# waterLevelDisplay.net
KiCad netlist of a schematic drawn in EAGLE
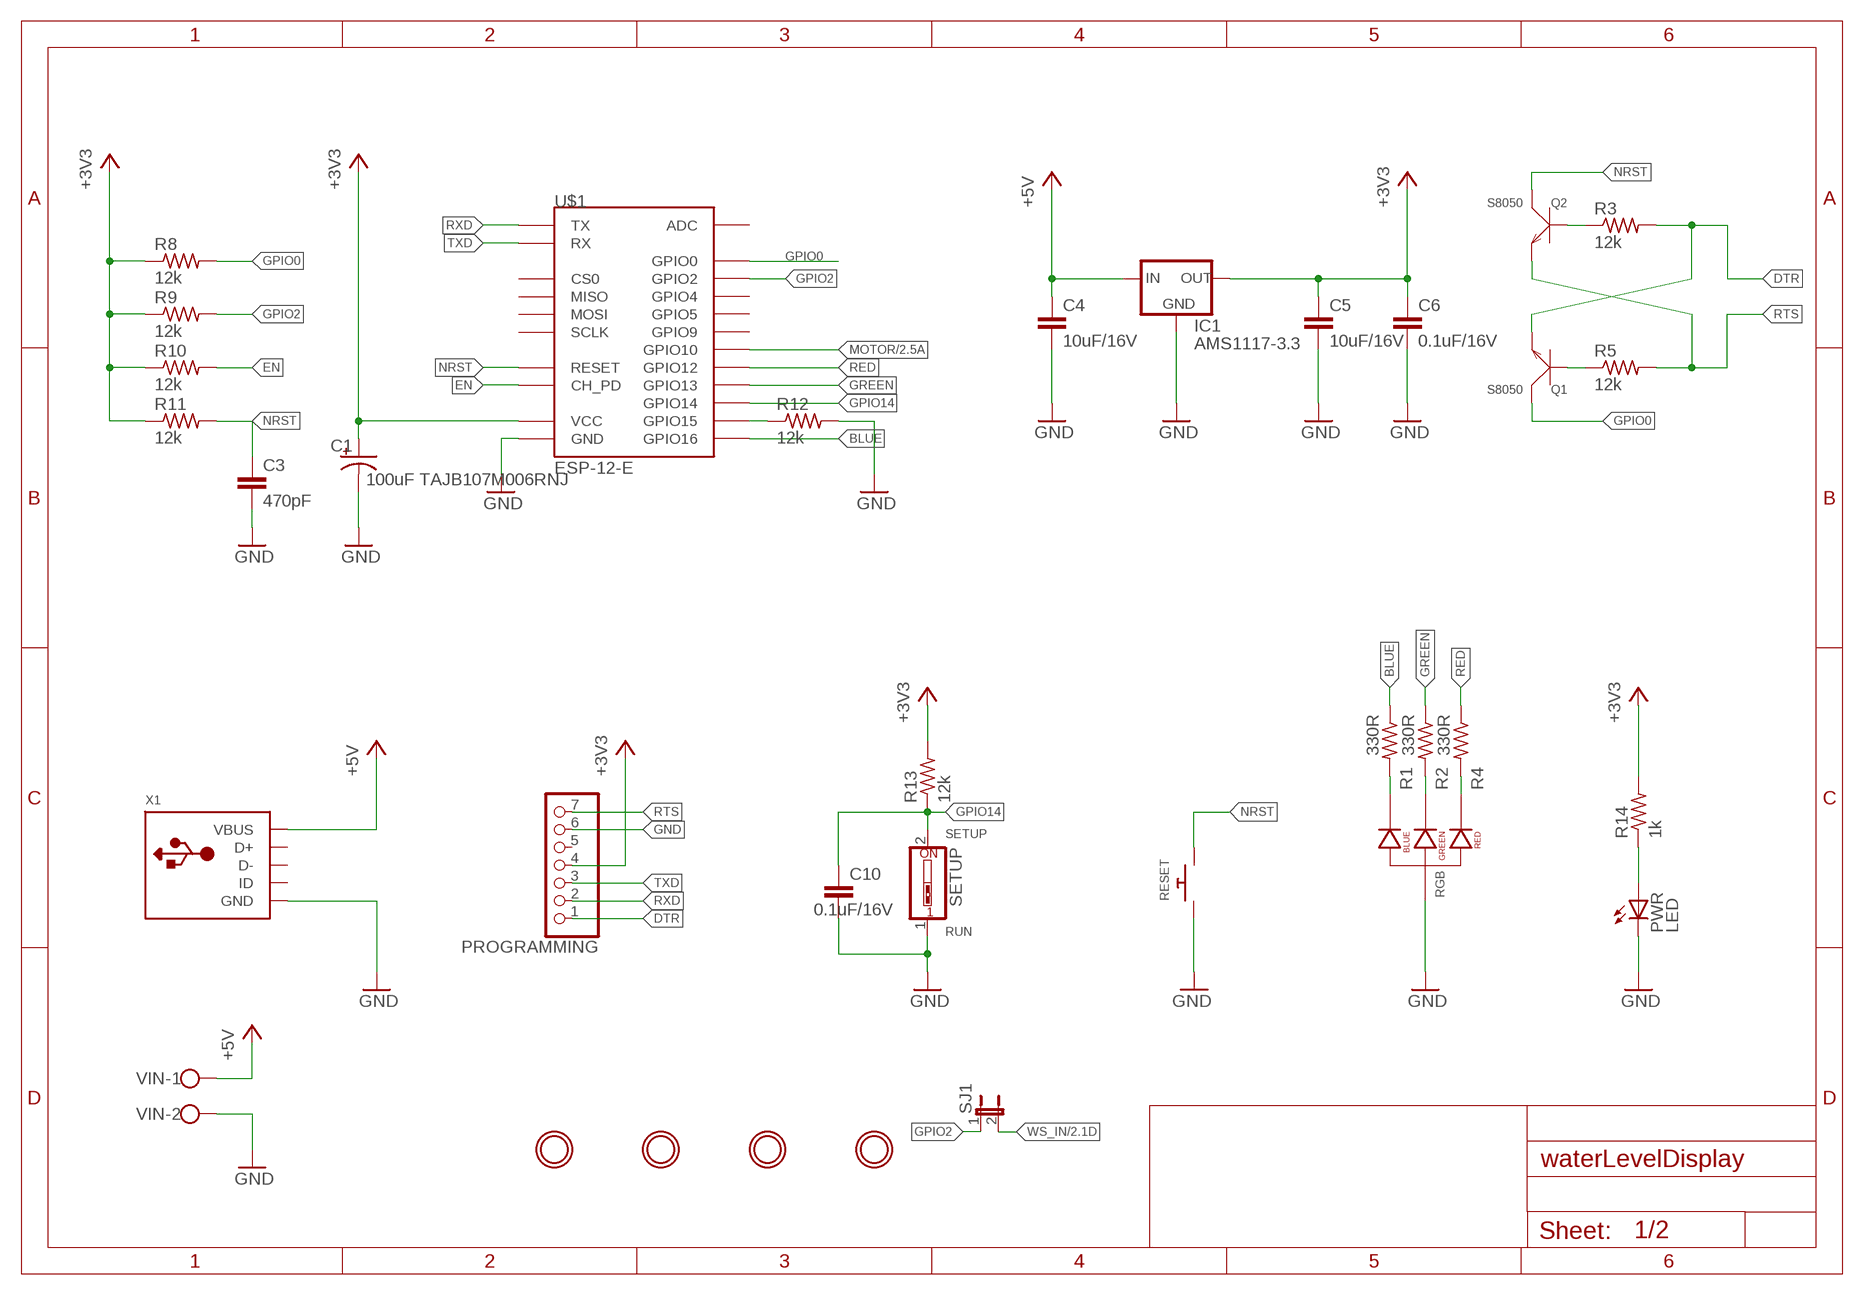
[diagram p0: schematic, sheet 1]
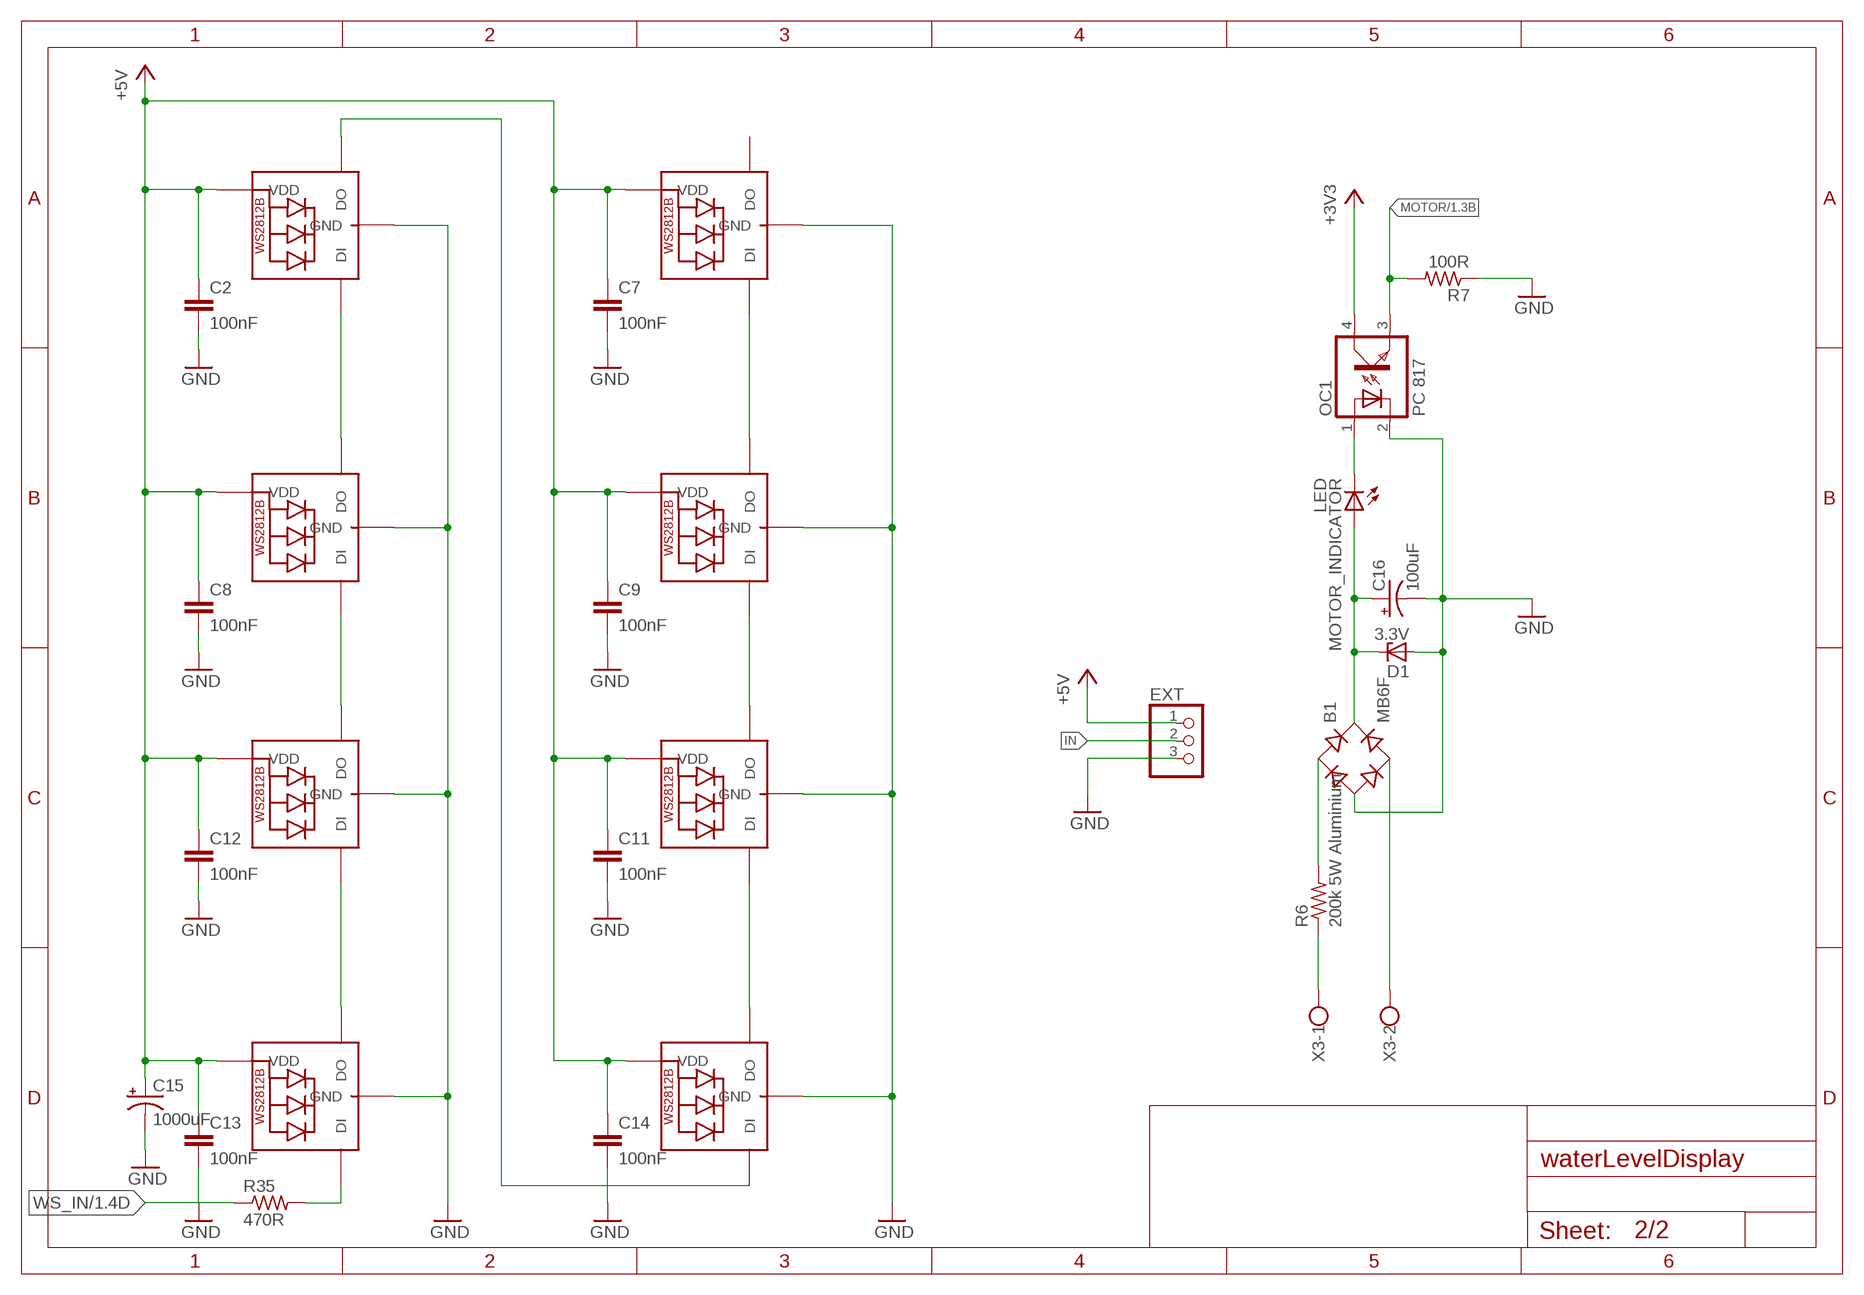
[diagram p1: schematic, sheet 2]

(export (version "E")
  (design (tool "Eeschema 10.0.6"))
  (components
    (comp (ref "B1")
      (value "MB6F")
      (footprint "eagle-import:SOIC-4")
      (libsource (lib "eagle-import") (part "MBS6"))
    )
    (comp (ref "C2")
      (value "100nF")
      (footprint "eagle-import:C0805K")
      (libsource (lib "eagle-import") (part "C-EUC0805K"))
    )
    (comp (ref "C7")
      (value "100nF")
      (footprint "eagle-import:C0805K")
      (libsource (lib "eagle-import") (part "C-EUC0805K"))
    )
    (comp (ref "C8")
      (value "100nF")
      (footprint "eagle-import:C0805K")
      (libsource (lib "eagle-import") (part "C-EUC0805K"))
    )
    (comp (ref "C9")
      (value "100nF")
      (footprint "eagle-import:C0805K")
      (libsource (lib "eagle-import") (part "C-EUC0805K"))
    )
    (comp (ref "C11")
      (value "100nF")
      (footprint "eagle-import:C0805K")
      (libsource (lib "eagle-import") (part "C-EUC0805K"))
    )
    (comp (ref "C12")
      (value "100nF")
      (footprint "eagle-import:C0805K")
      (libsource (lib "eagle-import") (part "C-EUC0805K"))
    )
    (comp (ref "C13")
      (value "100nF")
      (footprint "eagle-import:C0805K")
      (libsource (lib "eagle-import") (part "C-EUC0805K"))
    )
    (comp (ref "C14")
      (value "100nF")
      (footprint "eagle-import:C0805K")
      (libsource (lib "eagle-import") (part "C-EUC0805K"))
    )
    (comp (ref "C15")
      (value "1000uF")
      (footprint "eagle-import:E5-10,5")
      (libsource (lib "eagle-import") (part "CPOL-USE5-10.5"))
    )
    (comp (ref "C16")
      (value "100uF")
      (footprint "eagle-import:E2,5-7")
      (libsource (lib "eagle-import") (part "CPOL-USE2.5-7"))
    )
    (comp (ref "D1")
      (value "3.3V")
      (footprint "eagle-import:ZDIO-7.5")
      (libsource (lib "eagle-import") (part "ZENER-DIODEZD-7.5"))
    )
    (comp (ref "EXT")
      (value "PINHD-1X3")
      (footprint "eagle-import:1X03")
      (libsource (lib "eagle-import") (part "PINHD-1X3"))
    )
    (comp (ref "LED1")
      (value "WS2812B5050")
      (footprint "eagle-import:WS2812B")
      (libsource (lib "eagle-import") (part "WS2812B5050"))
    )
    (comp (ref "LED2")
      (value "WS2812B5050")
      (footprint "eagle-import:WS2812B")
      (libsource (lib "eagle-import") (part "WS2812B5050"))
    )
    (comp (ref "LED3")
      (value "WS2812B5050")
      (footprint "eagle-import:WS2812B")
      (libsource (lib "eagle-import") (part "WS2812B5050"))
    )
    (comp (ref "LED4")
      (value "WS2812B5050")
      (footprint "eagle-import:WS2812B")
      (libsource (lib "eagle-import") (part "WS2812B5050"))
    )
    (comp (ref "LED5")
      (value "WS2812B5050")
      (footprint "eagle-import:WS2812B")
      (libsource (lib "eagle-import") (part "WS2812B5050"))
    )
    (comp (ref "LED6")
      (value "WS2812B5050")
      (footprint "eagle-import:WS2812B")
      (libsource (lib "eagle-import") (part "WS2812B5050"))
    )
    (comp (ref "LED7")
      (value "WS2812B5050")
      (footprint "eagle-import:WS2812B")
      (libsource (lib "eagle-import") (part "WS2812B5050"))
    )
    (comp (ref "LED8")
      (value "WS2812B5050")
      (footprint "eagle-import:WS2812B")
      (libsource (lib "eagle-import") (part "WS2812B5050"))
    )
    (comp (ref "MOTOR_INDICATOR")
      (value "LED")
      (footprint "eagle-import:CHIP-LED0805")
      (libsource (lib "eagle-import") (part "LEDCHIP-LED0805"))
    )
    (comp (ref "OC1")
      (value "PC 817")
      (footprint "eagle-import:DIP4")
      (fields (field (name "MF") "VISHAY/TELEFUNKEN") (field (name "MPN") "SFH618A-3"))
      (libsource (lib "eagle-import") (part "SFH618?A-3"))
    )
    (comp (ref "R6")
      (value "200k 5W Aluminium")
      (footprint "eagle-import:0617_22")
      (libsource (lib "eagle-import") (part "R-US_0617/22"))
    )
    (comp (ref "R7")
      (value "100R")
      (footprint "eagle-import:M0805")
      (libsource (lib "eagle-import") (part "R-US_M0805"))
    )
    (comp (ref "R35")
      (value "470R")
      (footprint "eagle-import:M0805")
      (libsource (lib "eagle-import") (part "R-US_M0805"))
    )
    (comp (ref "X3")
      (value "W237-102")
      (footprint "eagle-import:W237-102")
      (fields (field (name "MPN") "237-102"))
      (libsource (lib "eagle-import") (part "W237-102"))
    )
    (comp (ref "C1")
      (value "100uF TAJB107M006RNJ")
      (footprint "eagle-import:A_3216-18R")
      (libsource (lib "eagle-import") (part "CPOL-USA/3216-18R"))
    )
    (comp (ref "C3")
      (value "470pF")
      (footprint "eagle-import:C0805K")
      (libsource (lib "eagle-import") (part "C-EUC0805K"))
    )
    (comp (ref "C4")
      (value "10uF/16V")
      (footprint "eagle-import:C0805K")
      (libsource (lib "eagle-import") (part "C-EUC0805K"))
    )
    (comp (ref "C5")
      (value "10uF/16V")
      (footprint "eagle-import:C0805K")
      (libsource (lib "eagle-import") (part "C-EUC0805K"))
    )
    (comp (ref "C6")
      (value "0.1uF/16V")
      (footprint "eagle-import:C0805K")
      (libsource (lib "eagle-import") (part "C-EUC0805K"))
    )
    (comp (ref "C10")
      (value "0.1uF/16V")
      (footprint "eagle-import:C0805K")
      (libsource (lib "eagle-import") (part "C-EUC0805K"))
    )
    (comp (ref "IC1")
      (value "AMS1117-3.3")
      (footprint "eagle-import:SOT223")
      (libsource (lib "eagle-import") (part "LM1117"))
    )
    (comp (ref "PROGRAMMING")
      (value "PINHD-1X7")
      (footprint "eagle-import:1X07")
      (libsource (lib "eagle-import") (part "PINHD-1X7"))
    )
    (comp (ref "PWR")
      (value "LED")
      (footprint "eagle-import:CHIP-LED0805")
      (libsource (lib "eagle-import") (part "LEDCHIP-LED0805"))
    )
    (comp (ref "Q1")
      (value "S8050")
      (footprint "eagle-import:SOT-23")
      (fields (field (name "MF") "JCET"))
      (libsource (lib "eagle-import") (part "SMD-TRANSISTORS-NPN-25V-500MW(SOT-23)"))
    )
    (comp (ref "Q2")
      (value "S8050")
      (footprint "eagle-import:SOT-23")
      (fields (field (name "MF") "JCET"))
      (libsource (lib "eagle-import") (part "SMD-TRANSISTORS-NPN-25V-500MW(SOT-23)"))
    )
    (comp (ref "R1")
      (value "330R")
      (footprint "eagle-import:M0805")
      (libsource (lib "eagle-import") (part "R-US_M0805"))
    )
    (comp (ref "R2")
      (value "330R")
      (footprint "eagle-import:M0805")
      (libsource (lib "eagle-import") (part "R-US_M0805"))
    )
    (comp (ref "R3")
      (value "12k")
      (footprint "eagle-import:M0805")
      (libsource (lib "eagle-import") (part "R-US_M0805"))
    )
    (comp (ref "R4")
      (value "330R")
      (footprint "eagle-import:M0805")
      (libsource (lib "eagle-import") (part "R-US_M0805"))
    )
    (comp (ref "R5")
      (value "12k")
      (footprint "eagle-import:M0805")
      (libsource (lib "eagle-import") (part "R-US_M0805"))
    )
    (comp (ref "R8")
      (value "12k")
      (footprint "eagle-import:M0805")
      (libsource (lib "eagle-import") (part "R-US_M0805"))
    )
    (comp (ref "R9")
      (value "12k")
      (footprint "eagle-import:M0805")
      (libsource (lib "eagle-import") (part "R-US_M0805"))
    )
    (comp (ref "R10")
      (value "12k")
      (footprint "eagle-import:M0805")
      (libsource (lib "eagle-import") (part "R-US_M0805"))
    )
    (comp (ref "R11")
      (value "12k")
      (footprint "eagle-import:M0805")
      (libsource (lib "eagle-import") (part "R-US_M0805"))
    )
    (comp (ref "R12")
      (value "12k")
      (footprint "eagle-import:M0805")
      (libsource (lib "eagle-import") (part "R-US_M0805"))
    )
    (comp (ref "R13")
      (value "12k")
      (footprint "eagle-import:M0805")
      (libsource (lib "eagle-import") (part "R-US_M0805"))
    )
    (comp (ref "R14")
      (value "1k")
      (footprint "eagle-import:M0805")
      (libsource (lib "eagle-import") (part "R-US_M0805"))
    )
    (comp (ref "RESET")
      (value "SWITCH_PUSHBUTTONEVQ-PE")
      (footprint "eagle-import:TACT_PANA-EVQ")
      (libsource (lib "eagle-import") (part "SWITCH_PUSHBUTTONEVQ-PE"))
    )
    (comp (ref "RGB")
      (value "LED-RGB-CA-THRUCLEAR")
      (footprint "eagle-import:LED-RGB-THRU")
      (libsource (lib "eagle-import") (part "LED-RGB-CA-THRUCLEAR"))
    )
    (comp (ref "SETUP")
      (value "SW_DIP-1")
      (footprint "eagle-import:EDG-01")
      (libsource (lib "eagle-import") (part "SW_DIP-1"))
    )
    (comp (ref "SJ1")
      (value "SPARKFUN-PASSIVES_JUMPER-PTH-2-NC")
      (footprint "eagle-import:SPARKFUN-PASSIVES_PTH-JUMPER-NC_BOTTOM_NO_SILK")
      (libsource (lib "eagle-import") (part "SPARKFUN-PASSIVES_JUMPER-PTH-2-NC"))
    )
    (comp (ref "U$1")
      (value "ESP-12-E")
      (footprint "eagle-import:ESP-12-E")
      (libsource (lib "eagle-import") (part "ESP-12-E"))
    )
    (comp (ref "U$3")
      (value "MOUNTINGHOLE2.5")
      (footprint "eagle-import:MOUNTINGHOLE_2.5_PLATED")
      (libsource (lib "eagle-import") (part "MOUNTINGHOLE2.5"))
    )
    (comp (ref "U$4")
      (value "MOUNTINGHOLE2.5")
      (footprint "eagle-import:MOUNTINGHOLE_2.5_PLATED")
      (libsource (lib "eagle-import") (part "MOUNTINGHOLE2.5"))
    )
    (comp (ref "U$5")
      (value "MOUNTINGHOLE2.5")
      (footprint "eagle-import:MOUNTINGHOLE_2.5_PLATED")
      (libsource (lib "eagle-import") (part "MOUNTINGHOLE2.5"))
    )
    (comp (ref "U$6")
      (value "MOUNTINGHOLE2.5")
      (footprint "eagle-import:MOUNTINGHOLE_2.5_PLATED")
      (libsource (lib "eagle-import") (part "MOUNTINGHOLE2.5"))
    )
    (comp (ref "VIN")
      (value "W237-102")
      (footprint "eagle-import:W237-102")
      (fields (field (name "MPN") "237-102"))
      (libsource (lib "eagle-import") (part "W237-102"))
    )
    (comp (ref "X1")
      (value "USB_MICRO_20329_V2")
      (footprint "eagle-import:4UCONN_20329_V2")
      (libsource (lib "eagle-import") (part "USB_MICRO_20329_V2"))
    )
  )
  (nets
    (net (code "1") (name "+3V3") (class "Default")
      (node (ref "C1") (pin "+") (pinfunction "+_+") (pintype "passive"))
      (node (ref "C5") (pin "1") (pinfunction "1_1") (pintype "passive"))
      (node (ref "C6") (pin "1") (pinfunction "1_1") (pintype "passive"))
      (node (ref "IC1") (pin "2") (pinfunction "OUT_2") (pintype "passive"))
      (node (ref "OC1") (pin "4") (pinfunction "COL_4") (pintype "passive"))
      (node (ref "PROGRAMMING") (pin "4") (pinfunction "4_4") (pintype "passive"))
      (node (ref "R10") (pin "1") (pinfunction "1_1") (pintype "passive"))
      (node (ref "R11") (pin "1") (pinfunction "1_1") (pintype "passive"))
      (node (ref "R13") (pin "2") (pinfunction "2_2") (pintype "passive"))
      (node (ref "R14") (pin "2") (pinfunction "2_2") (pintype "passive"))
      (node (ref "R8") (pin "1") (pinfunction "1_1") (pintype "passive"))
      (node (ref "R9") (pin "1") (pinfunction "1_1") (pintype "passive"))
      (node (ref "U$1") (pin "VCC") (pinfunction "VCC_VCC") (pintype "bidirectional"))
    )
    (net (code "2") (name "+5V") (class "Default")
      (node (ref "C11") (pin "1") (pinfunction "1_1") (pintype "passive"))
      (node (ref "C12") (pin "1") (pinfunction "1_1") (pintype "passive"))
      (node (ref "C13") (pin "1") (pinfunction "1_1") (pintype "passive"))
      (node (ref "C14") (pin "1") (pinfunction "1_1") (pintype "passive"))
      (node (ref "C15") (pin "+") (pinfunction "+_+") (pintype "passive"))
      (node (ref "C2") (pin "1") (pinfunction "1_1") (pintype "passive"))
      (node (ref "C4") (pin "1") (pinfunction "1_1") (pintype "passive"))
      (node (ref "C7") (pin "1") (pinfunction "1_1") (pintype "passive"))
      (node (ref "C8") (pin "1") (pinfunction "1_1") (pintype "passive"))
      (node (ref "C9") (pin "1") (pinfunction "1_1") (pintype "passive"))
      (node (ref "EXT") (pin "1") (pinfunction "1_1") (pintype "passive"))
      (node (ref "IC1") (pin "3") (pinfunction "IN_3") (pintype "input"))
      (node (ref "LED1") (pin "1-VDD") (pinfunction "VDD_1-VDD") (pintype "power_in"))
      (node (ref "LED2") (pin "1-VDD") (pinfunction "VDD_1-VDD") (pintype "power_in"))
      (node (ref "LED3") (pin "1-VDD") (pinfunction "VDD_1-VDD") (pintype "power_in"))
      (node (ref "LED4") (pin "1-VDD") (pinfunction "VDD_1-VDD") (pintype "power_in"))
      (node (ref "LED5") (pin "1-VDD") (pinfunction "VDD_1-VDD") (pintype "power_in"))
      (node (ref "LED6") (pin "1-VDD") (pinfunction "VDD_1-VDD") (pintype "power_in"))
      (node (ref "LED7") (pin "1-VDD") (pinfunction "VDD_1-VDD") (pintype "power_in"))
      (node (ref "LED8") (pin "1-VDD") (pinfunction "VDD_1-VDD") (pintype "power_in"))
      (node (ref "VIN") (pin "1") (pinfunction "KL_1") (pintype "passive"))
      (node (ref "X1") (pin "VBUS") (pinfunction "VBUS_VBUS") (pintype "power_in"))
    )
    (net (code "3") (name "BLUE") (class "Default")
      (node (ref "R1") (pin "1") (pinfunction "1_1") (pintype "passive"))
      (node (ref "U$1") (pin "GPIO16") (pinfunction "GPIO16_GPIO16") (pintype "bidirectional"))
    )
    (net (code "4") (name "DTR") (class "Default")
      (node (ref "PROGRAMMING") (pin "1") (pinfunction "1_1") (pintype "passive"))
      (node (ref "Q1") (pin "2") (pinfunction "E_2") (pintype "passive"))
      (node (ref "R3") (pin "2") (pinfunction "2_2") (pintype "passive"))
    )
    (net (code "5") (name "EN") (class "Default")
      (node (ref "R10") (pin "2") (pinfunction "2_2") (pintype "passive"))
      (node (ref "U$1") (pin "CH_PD") (pinfunction "CH_PD_CH_PD") (pintype "bidirectional"))
    )
    (net (code "6") (name "GND") (class "Default")
      (node (ref "B1") (pin "-") (pinfunction "-_-") (pintype "passive"))
      (node (ref "C1") (pin "-") (pinfunction "-_-") (pintype "passive"))
      (node (ref "C10") (pin "2") (pinfunction "2_2") (pintype "passive"))
      (node (ref "C11") (pin "2") (pinfunction "2_2") (pintype "passive"))
      (node (ref "C12") (pin "2") (pinfunction "2_2") (pintype "passive"))
      (node (ref "C13") (pin "2") (pinfunction "2_2") (pintype "passive"))
      (node (ref "C14") (pin "2") (pinfunction "2_2") (pintype "passive"))
      (node (ref "C15") (pin "-") (pinfunction "-_-") (pintype "passive"))
      (node (ref "C16") (pin "-") (pinfunction "-_-") (pintype "passive"))
      (node (ref "C2") (pin "2") (pinfunction "2_2") (pintype "passive"))
      (node (ref "C3") (pin "2") (pinfunction "2_2") (pintype "passive"))
      (node (ref "C4") (pin "2") (pinfunction "2_2") (pintype "passive"))
      (node (ref "C5") (pin "2") (pinfunction "2_2") (pintype "passive"))
      (node (ref "C6") (pin "2") (pinfunction "2_2") (pintype "passive"))
      (node (ref "C7") (pin "2") (pinfunction "2_2") (pintype "passive"))
      (node (ref "C8") (pin "2") (pinfunction "2_2") (pintype "passive"))
      (node (ref "C9") (pin "2") (pinfunction "2_2") (pintype "passive"))
      (node (ref "D1") (pin "A") (pinfunction "A_A") (pintype "passive"))
      (node (ref "EXT") (pin "3") (pinfunction "3_3") (pintype "passive"))
      (node (ref "IC1") (pin "1") (pinfunction "GND_1") (pintype "input"))
      (node (ref "LED1") (pin "3-GND") (pinfunction "GND_3-GND") (pintype "power_in"))
      (node (ref "LED2") (pin "3-GND") (pinfunction "GND_3-GND") (pintype "power_in"))
      (node (ref "LED3") (pin "3-GND") (pinfunction "GND_3-GND") (pintype "power_in"))
      (node (ref "LED4") (pin "3-GND") (pinfunction "GND_3-GND") (pintype "power_in"))
      (node (ref "LED5") (pin "3-GND") (pinfunction "GND_3-GND") (pintype "power_in"))
      (node (ref "LED6") (pin "3-GND") (pinfunction "GND_3-GND") (pintype "power_in"))
      (node (ref "LED7") (pin "3-GND") (pinfunction "GND_3-GND") (pintype "power_in"))
      (node (ref "LED8") (pin "3-GND") (pinfunction "GND_3-GND") (pintype "power_in"))
      (node (ref "OC1") (pin "2") (pinfunction "C_2") (pintype "passive"))
      (node (ref "PROGRAMMING") (pin "6") (pinfunction "6_6") (pintype "passive"))
      (node (ref "PWR") (pin "C") (pinfunction "C_C") (pintype "passive"))
      (node (ref "R12") (pin "2") (pinfunction "2_2") (pintype "passive"))
      (node (ref "R7") (pin "1") (pinfunction "1_1") (pintype "passive"))
      (node (ref "RESET") (pin "P$1") (pinfunction "P$1_P$1") (pintype "passive"))
      (node (ref "RGB") (pin "2") (pinfunction "ANODE_2") (pintype "bidirectional"))
      (node (ref "SETUP") (pin "1") (pinfunction "1_1") (pintype "passive"))
      (node (ref "U$1") (pin "GND") (pinfunction "GND_GND") (pintype "bidirectional"))
      (node (ref "VIN") (pin "2") (pinfunction "KL_2") (pintype "passive"))
      (node (ref "X1") (pin "BASE@1") (pinfunction "GND_BASE@1") (pintype "power_in"))
      (node (ref "X1") (pin "BASE@2") (pinfunction "GND_BASE@2") (pintype "power_in"))
      (node (ref "X1") (pin "GND") (pinfunction "GND_GND") (pintype "power_in"))
      (node (ref "X1") (pin "SPRT@1") (pinfunction "GND_SPRT@1") (pintype "power_in"))
      (node (ref "X1") (pin "SPRT@2") (pinfunction "GND_SPRT@2") (pintype "power_in"))
      (node (ref "X1") (pin "SPRT@3") (pinfunction "GND_SPRT@3") (pintype "power_in"))
      (node (ref "X1") (pin "SPRT@4") (pinfunction "GND_SPRT@4") (pintype "power_in"))
    )
    (net (code "7") (name "GPIO0") (class "Default")
      (node (ref "Q1") (pin "3") (pinfunction "C_3") (pintype "passive"))
      (node (ref "R8") (pin "2") (pinfunction "2_2") (pintype "passive"))
      (node (ref "U$1") (pin "GPIO0") (pinfunction "GPIO0_GPIO0") (pintype "bidirectional"))
    )
    (net (code "8") (name "GPIO2") (class "Default")
      (node (ref "R9") (pin "2") (pinfunction "2_2") (pintype "passive"))
      (node (ref "SJ1") (pin "1") (pinfunction "1_1") (pintype "passive"))
      (node (ref "U$1") (pin "GPIO2") (pinfunction "GPIO2_GPIO2") (pintype "bidirectional"))
    )
    (net (code "9") (name "GPIO14") (class "Default")
      (node (ref "C10") (pin "1") (pinfunction "1_1") (pintype "passive"))
      (node (ref "R13") (pin "1") (pinfunction "1_1") (pintype "passive"))
      (node (ref "SETUP") (pin "2") (pinfunction "2_2") (pintype "passive"))
      (node (ref "U$1") (pin "GPIO14") (pinfunction "GPIO14_GPIO14") (pintype "bidirectional"))
    )
    (net (code "10") (name "GREEN") (class "Default")
      (node (ref "R2") (pin "1") (pinfunction "1_1") (pintype "passive"))
      (node (ref "U$1") (pin "GPIO13") (pinfunction "GPIO13_GPIO13") (pintype "bidirectional"))
    )
    (net (code "11") (name "IN") (class "Default")
      (node (ref "EXT") (pin "2") (pinfunction "2_2") (pintype "passive"))
      (node (ref "LED8") (pin "4-DIN") (pinfunction "DI_4-DIN") (pintype "input"))
      (node (ref "R35") (pin "2") (pinfunction "2_2") (pintype "passive"))
    )
    (net (code "12") (name "MOTOR") (class "Default")
      (node (ref "OC1") (pin "3") (pinfunction "EMIT_3") (pintype "passive"))
      (node (ref "R7") (pin "2") (pinfunction "2_2") (pintype "passive"))
      (node (ref "U$1") (pin "GPIO10") (pinfunction "GPIO10_GPIO10") (pintype "bidirectional"))
    )
    (net (code "13") (name "NRST") (class "Default")
      (node (ref "C3") (pin "1") (pinfunction "1_1") (pintype "passive"))
      (node (ref "Q2") (pin "3") (pinfunction "C_3") (pintype "passive"))
      (node (ref "R11") (pin "2") (pinfunction "2_2") (pintype "passive"))
      (node (ref "RESET") (pin "P$2") (pinfunction "P$2_P$2") (pintype "passive"))
      (node (ref "U$1") (pin "RESET") (pinfunction "RESET_RESET") (pintype "bidirectional"))
    )
    (net (code "14") (name "Net-(B1-AC1)") (class "Default")
      (node (ref "B1") (pin "~1") (pinfunction "AC1_~1") (pintype "passive"))
      (node (ref "R6") (pin "2") (pinfunction "2_2") (pintype "passive"))
    )
    (net (code "15") (name "Net-(B1-AC2)") (class "Default")
      (node (ref "B1") (pin "~2") (pinfunction "AC2_~2") (pintype "passive"))
      (node (ref "X3") (pin "2") (pinfunction "KL_2") (pintype "passive"))
    )
    (net (code "16") (name "Net-(B1-Pad+)") (class "Default")
      (node (ref "B1") (pin "+") (pinfunction "+_+") (pintype "passive"))
      (node (ref "C16") (pin "+") (pinfunction "+_+") (pintype "passive"))
      (node (ref "D1") (pin "C") (pinfunction "C_C") (pintype "passive"))
      (node (ref "MOTOR_INDICATOR") (pin "A") (pinfunction "A_A") (pintype "passive"))
    )
    (net (code "17") (name "Net-(LED1-DI)") (class "Default")
      (node (ref "LED1") (pin "4-DIN") (pinfunction "DI_4-DIN") (pintype "input"))
      (node (ref "LED3") (pin "2-DOUT") (pinfunction "DO_2-DOUT") (pintype "output"))
    )
    (net (code "18") (name "Net-(LED1-DO)") (class "Default")
      (node (ref "LED1") (pin "2-DOUT") (pinfunction "DO_2-DOUT") (pintype "output"))
      (node (ref "LED7") (pin "4-DIN") (pinfunction "DI_4-DIN") (pintype "input"))
    )
    (net (code "19") (name "Net-(LED2-DI)") (class "Default")
      (node (ref "LED2") (pin "4-DIN") (pinfunction "DI_4-DIN") (pintype "input"))
      (node (ref "LED4") (pin "2-DOUT") (pinfunction "DO_2-DOUT") (pintype "output"))
    )
    (net (code "20") (name "Net-(LED3-DI)") (class "Default")
      (node (ref "LED3") (pin "4-DIN") (pinfunction "DI_4-DIN") (pintype "input"))
      (node (ref "LED5") (pin "2-DOUT") (pinfunction "DO_2-DOUT") (pintype "output"))
    )
    (net (code "21") (name "Net-(LED4-DI)") (class "Default")
      (node (ref "LED4") (pin "4-DIN") (pinfunction "DI_4-DIN") (pintype "input"))
      (node (ref "LED6") (pin "2-DOUT") (pinfunction "DO_2-DOUT") (pintype "output"))
    )
    (net (code "22") (name "Net-(LED5-DI)") (class "Default")
      (node (ref "LED5") (pin "4-DIN") (pinfunction "DI_4-DIN") (pintype "input"))
      (node (ref "LED8") (pin "2-DOUT") (pinfunction "DO_2-DOUT") (pintype "output"))
    )
    (net (code "23") (name "Net-(LED6-DI)") (class "Default")
      (node (ref "LED6") (pin "4-DIN") (pinfunction "DI_4-DIN") (pintype "input"))
      (node (ref "LED7") (pin "2-DOUT") (pinfunction "DO_2-DOUT") (pintype "output"))
    )
    (net (code "24") (name "Net-(OC1-A)") (class "Default")
      (node (ref "MOTOR_INDICATOR") (pin "C") (pinfunction "C_C") (pintype "passive"))
      (node (ref "OC1") (pin "1") (pinfunction "A_1") (pintype "passive"))
    )
    (net (code "25") (name "Net-(PWR-PadA)") (class "Default")
      (node (ref "PWR") (pin "A") (pinfunction "A_A") (pintype "passive"))
      (node (ref "R14") (pin "1") (pinfunction "1_1") (pintype "passive"))
    )
    (net (code "26") (name "Net-(Q1-B)") (class "Default")
      (node (ref "Q1") (pin "1") (pinfunction "B_1") (pintype "passive"))
      (node (ref "R5") (pin "1") (pinfunction "1_1") (pintype "passive"))
    )
    (net (code "27") (name "Net-(Q2-B)") (class "Default")
      (node (ref "Q2") (pin "1") (pinfunction "B_1") (pintype "passive"))
      (node (ref "R3") (pin "1") (pinfunction "1_1") (pintype "passive"))
    )
    (net (code "28") (name "Net-(R12-Pad1)") (class "Default")
      (node (ref "R12") (pin "1") (pinfunction "1_1") (pintype "passive"))
      (node (ref "U$1") (pin "GPIO15") (pinfunction "GPIO15_GPIO15") (pintype "bidirectional"))
    )
    (net (code "29") (name "Net-(RGB-BLUE_CATHODE)") (class "Default")
      (node (ref "R1") (pin "2") (pinfunction "2_2") (pintype "passive"))
      (node (ref "RGB") (pin "4") (pinfunction "BLUE_CATHODE_4") (pintype "bidirectional"))
    )
    (net (code "30") (name "Net-(RGB-GREEN_CATHODE)") (class "Default")
      (node (ref "R2") (pin "2") (pinfunction "2_2") (pintype "passive"))
      (node (ref "RGB") (pin "3") (pinfunction "GREEN_CATHODE_3") (pintype "bidirectional"))
    )
    (net (code "31") (name "Net-(RGB-RED_CATHODE)") (class "Default")
      (node (ref "R4") (pin "2") (pinfunction "2_2") (pintype "passive"))
      (node (ref "RGB") (pin "1") (pinfunction "RED_CATHODE_1") (pintype "bidirectional"))
    )
    (net (code "32") (name "Net-(X3A-KL)") (class "Default")
      (node (ref "R6") (pin "1") (pinfunction "1_1") (pintype "passive"))
      (node (ref "X3") (pin "1") (pinfunction "KL_1") (pintype "passive"))
    )
    (net (code "33") (name "RED") (class "Default")
      (node (ref "R4") (pin "1") (pinfunction "1_1") (pintype "passive"))
      (node (ref "U$1") (pin "GPIO12") (pinfunction "GPIO12_GPIO12") (pintype "bidirectional"))
    )
    (net (code "34") (name "RTS") (class "Default")
      (node (ref "PROGRAMMING") (pin "7") (pinfunction "7_7") (pintype "passive"))
      (node (ref "Q2") (pin "2") (pinfunction "E_2") (pintype "passive"))
      (node (ref "R5") (pin "2") (pinfunction "2_2") (pintype "passive"))
    )
    (net (code "35") (name "RXD") (class "Default")
      (node (ref "PROGRAMMING") (pin "2") (pinfunction "2_2") (pintype "passive"))
      (node (ref "U$1") (pin "TX") (pinfunction "TX_TX") (pintype "bidirectional"))
    )
    (net (code "36") (name "TXD") (class "Default")
      (node (ref "PROGRAMMING") (pin "3") (pinfunction "3_3") (pintype "passive"))
      (node (ref "U$1") (pin "RX") (pinfunction "RX_RX") (pintype "bidirectional"))
    )
    (net (code "37") (name "WS_IN") (class "Default")
      (node (ref "R35") (pin "1") (pinfunction "1_1") (pintype "passive"))
      (node (ref "SJ1") (pin "2") (pinfunction "2_2") (pintype "passive"))
    )
    (net (code "38") (name "unconnected-(LED2-DO-Pad2-DOUT)") (class "Default")
      (node (ref "LED2") (pin "2-DOUT") (pinfunction "DO_2-DOUT") (pintype "output"))
    )
    (net (code "39") (name "unconnected-(PROGRAMMING-Pad5)") (class "Default")
      (node (ref "PROGRAMMING") (pin "5") (pinfunction "5_5") (pintype "passive"))
    )
    (net (code "40") (name "unconnected-(U$1-PadADC)") (class "Default")
      (node (ref "U$1") (pin "ADC") (pinfunction "ADC_ADC") (pintype "bidirectional"))
    )
    (net (code "41") (name "unconnected-(U$1-PadCS0)") (class "Default")
      (node (ref "U$1") (pin "CS0") (pinfunction "CS0_CS0") (pintype "bidirectional"))
    )
    (net (code "42") (name "unconnected-(U$1-PadGPIO4)") (class "Default")
      (node (ref "U$1") (pin "GPIO4") (pinfunction "GPIO4_GPIO4") (pintype "bidirectional"))
    )
    (net (code "43") (name "unconnected-(U$1-PadGPIO5)") (class "Default")
      (node (ref "U$1") (pin "GPIO5") (pinfunction "GPIO5_GPIO5") (pintype "bidirectional"))
    )
    (net (code "44") (name "unconnected-(U$1-PadGPIO9)") (class "Default")
      (node (ref "U$1") (pin "GPIO9") (pinfunction "GPIO9_GPIO9") (pintype "bidirectional"))
    )
    (net (code "45") (name "unconnected-(U$1-PadMISO)") (class "Default")
      (node (ref "U$1") (pin "MISO") (pinfunction "MISO_MISO") (pintype "bidirectional"))
    )
    (net (code "46") (name "unconnected-(U$1-PadMOSI)") (class "Default")
      (node (ref "U$1") (pin "MOSI") (pinfunction "MOSI_MOSI") (pintype "bidirectional"))
    )
    (net (code "47") (name "unconnected-(U$1-PadSCLK)") (class "Default")
      (node (ref "U$1") (pin "SCLK") (pinfunction "SCLK_SCLK") (pintype "bidirectional"))
    )
    (net (code "48") (name "unconnected-(X1-PadD+)") (class "Default")
      (node (ref "X1") (pin "D+") (pinfunction "D+_D+") (pintype "bidirectional"))
    )
    (net (code "49") (name "unconnected-(X1-PadD-)") (class "Default")
      (node (ref "X1") (pin "D-") (pinfunction "D-_D-") (pintype "bidirectional"))
    )
    (net (code "50") (name "unconnected-(X1-PadID)") (class "Default")
      (node (ref "X1") (pin "ID") (pinfunction "ID_ID") (pintype "bidirectional"))
    )
  )
)
